# schematic.net
KiCad netlist of a schematic drawn in EasyEDA
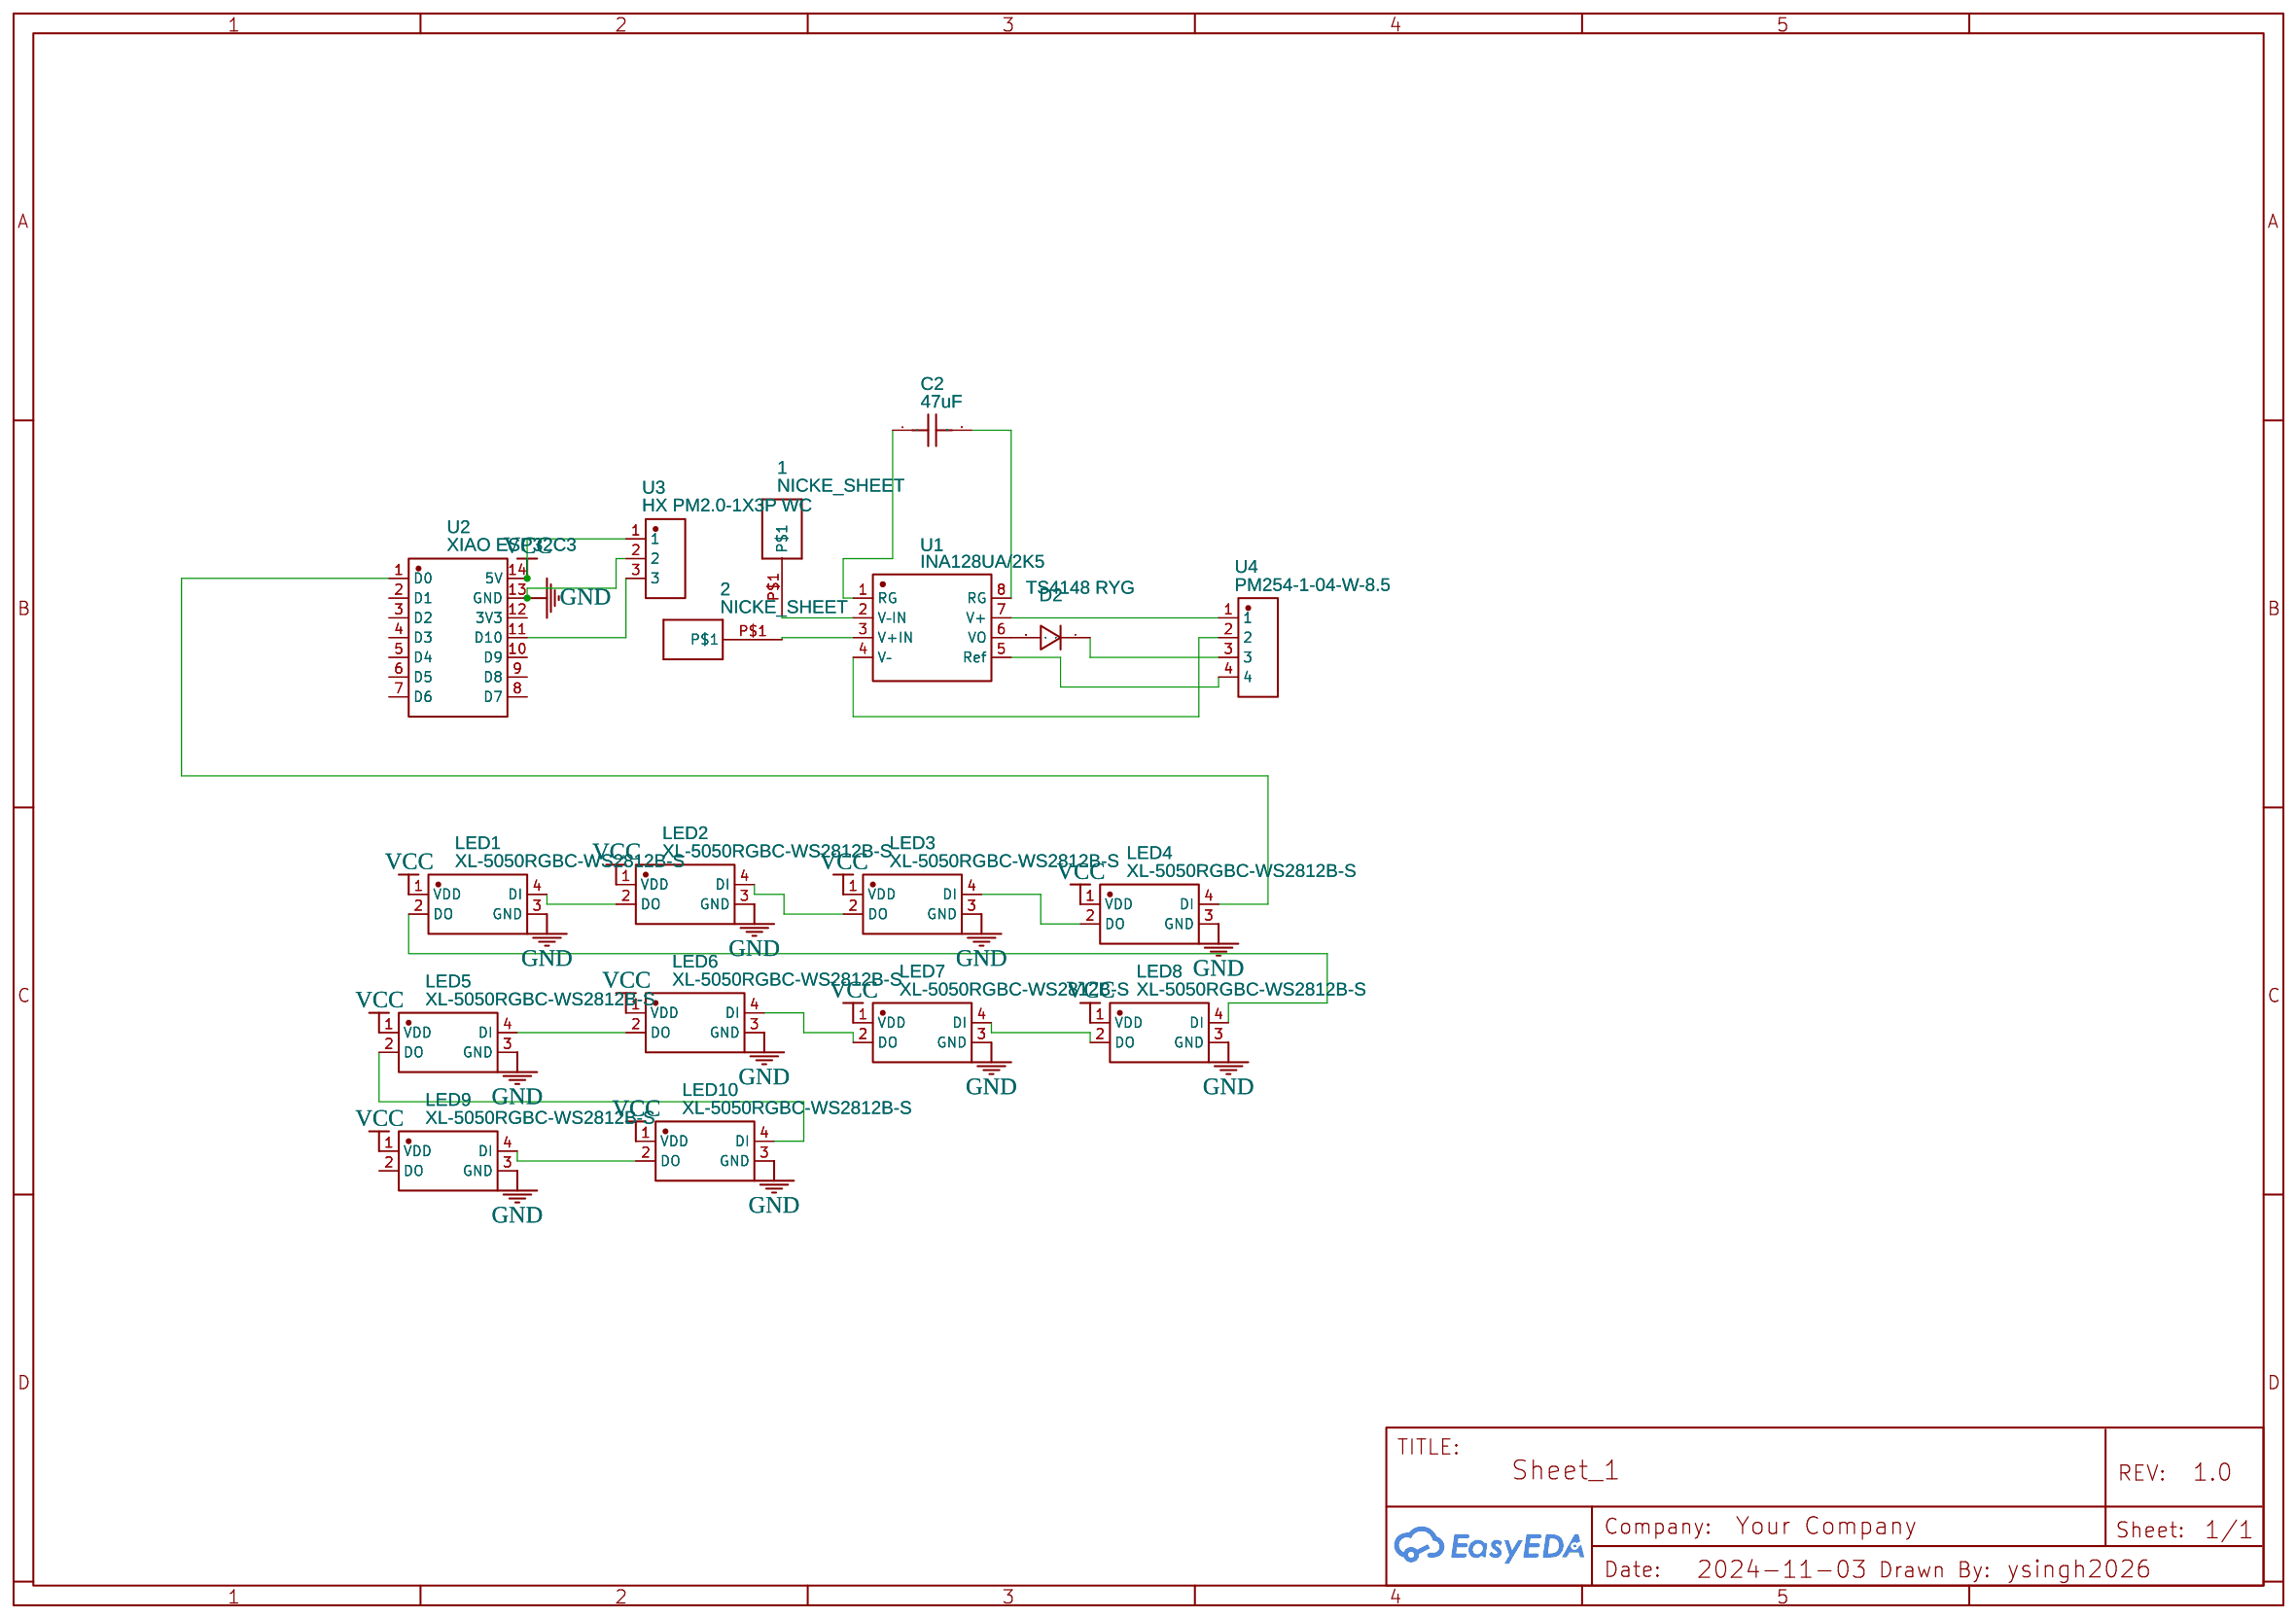
[diagram p0: schematic sheet]

(export (version "E")
  (design (tool "Eeschema 10.0.6"))
  (components
    (comp (ref "1") (value "NICKE_SHEET") (libsource (lib "") (part "NICKE_SHEET")))
    (comp (ref "2") (value "NICKE_SHEET") (libsource (lib "") (part "NICKE_SHEET_1")))
    (comp (ref "C2")
      (value "47uF")
      (fields
        (field (name "Manufacturer Part") "CS3225X7R476K100NRL")
        (field (name "Manufacturer") "SAMWHA(三和)")
      )
      (libsource (lib "") (part "CS3225X7R476K100NRL"))
    )
    (comp (ref "D2")
      (value "TS4148 RYG")
      (fields (field (name "Manufacturer") "Taiwan Semiconductor(台湾半导体)"))
      (libsource (lib "") (part "TS4148 RYG"))
    )
    (comp (ref "LED1")
      (value "XL-5050RGBC-WS2812B-S")
      (fields (field (name "Manufacturer") "XINGLIGHT(成兴光)"))
      (libsource (lib "") (part "XL-5050RGBC-WS2812B-S"))
    )
    (comp (ref "LED2")
      (value "XL-5050RGBC-WS2812B-S")
      (fields (field (name "Manufacturer") "XINGLIGHT(成兴光)"))
      (libsource (lib "") (part "XL-5050RGBC-WS2812B-S"))
    )
    (comp (ref "LED3")
      (value "XL-5050RGBC-WS2812B-S")
      (fields (field (name "Manufacturer") "XINGLIGHT(成兴光)"))
      (libsource (lib "") (part "XL-5050RGBC-WS2812B-S"))
    )
    (comp (ref "LED4")
      (value "XL-5050RGBC-WS2812B-S")
      (fields (field (name "Manufacturer") "XINGLIGHT(成兴光)"))
      (libsource (lib "") (part "XL-5050RGBC-WS2812B-S"))
    )
    (comp (ref "LED5")
      (value "XL-5050RGBC-WS2812B-S")
      (fields (field (name "Manufacturer") "XINGLIGHT(成兴光)"))
      (libsource (lib "") (part "XL-5050RGBC-WS2812B-S"))
    )
    (comp (ref "LED6")
      (value "XL-5050RGBC-WS2812B-S")
      (fields (field (name "Manufacturer") "XINGLIGHT(成兴光)"))
      (libsource (lib "") (part "XL-5050RGBC-WS2812B-S"))
    )
    (comp (ref "LED7")
      (value "XL-5050RGBC-WS2812B-S")
      (fields (field (name "Manufacturer") "XINGLIGHT(成兴光)"))
      (libsource (lib "") (part "XL-5050RGBC-WS2812B-S"))
    )
    (comp (ref "LED8")
      (value "XL-5050RGBC-WS2812B-S")
      (fields (field (name "Manufacturer") "XINGLIGHT(成兴光)"))
      (libsource (lib "") (part "XL-5050RGBC-WS2812B-S"))
    )
    (comp (ref "LED9")
      (value "XL-5050RGBC-WS2812B-S")
      (fields (field (name "Manufacturer") "XINGLIGHT(成兴光)"))
      (libsource (lib "") (part "XL-5050RGBC-WS2812B-S"))
    )
    (comp (ref "LED10")
      (value "XL-5050RGBC-WS2812B-S")
      (fields (field (name "Manufacturer") "XINGLIGHT(成兴光)"))
      (libsource (lib "") (part "XL-5050RGBC-WS2812B-S"))
    )
    (comp (ref "U1")
      (value "INA128UA/2K5")
      (fields (field (name "Manufacturer") "TI(德州仪器)"))
      (libsource (lib "") (part "INA128UA/2K5"))
    )
    (comp (ref "U2") (value "XIAO ESP32C3") (libsource (lib "") (part "XIAO ESP32C3")))
    (comp (ref "U3")
      (value "HX PM2.0-1X3P WC")
      (fields
        (field (name "Manufacturer Part") "HX PM2.0-1x3P WC")
        (field (name "Manufacturer") "hanxia(韩下)")
      )
      (libsource (lib "") (part "HX PM2.0-1X3P WC"))
    )
    (comp (ref "U4")
      (value "PM254-1-04-W-8.5")
      (fields (field (name "Manufacturer") "HCTL(华灿天禄)"))
      (libsource (lib "") (part "PM254-1-04-W-8.5"))
    )
  )
  (nets
    (net (code "1") (name "GND") (class "Default")
      (node (ref "LED1") (pin "3") (pinfunction "GND_3") (pintype "unspecified"))
      (node (ref "LED10") (pin "3") (pinfunction "GND_3") (pintype "unspecified"))
      (node (ref "LED2") (pin "3") (pinfunction "GND_3") (pintype "unspecified"))
      (node (ref "LED3") (pin "3") (pinfunction "GND_3") (pintype "unspecified"))
      (node (ref "LED4") (pin "3") (pinfunction "GND_3") (pintype "unspecified"))
      (node (ref "LED5") (pin "3") (pinfunction "GND_3") (pintype "unspecified"))
      (node (ref "LED6") (pin "3") (pinfunction "GND_3") (pintype "unspecified"))
      (node (ref "LED7") (pin "3") (pinfunction "GND_3") (pintype "unspecified"))
      (node (ref "LED8") (pin "3") (pinfunction "GND_3") (pintype "unspecified"))
      (node (ref "LED9") (pin "3") (pinfunction "GND_3") (pintype "unspecified"))
      (node (ref "U2") (pin "13") (pinfunction "GND_13") (pintype "unspecified"))
      (node (ref "U3") (pin "2") (pinfunction "2_2") (pintype "unspecified"))
    )
    (net (code "2") (name "Net-(C2-Pad1)") (class "Default")
      (node (ref "C2") (pin "1") (pinfunction "1_1") (pintype "unspecified"))
      (node (ref "U1") (pin "1") (pinfunction "RG_1") (pintype "unspecified"))
    )
    (net (code "3") (name "Net-(C2-Pad2)") (class "Default")
      (node (ref "C2") (pin "2") (pinfunction "2_2") (pintype "unspecified"))
      (node (ref "U1") (pin "8") (pinfunction "RG_8") (pintype "unspecified"))
    )
    (net (code "4") (name "Net-(D2-Pad1)") (class "Default")
      (node (ref "D2") (pin "1") (pinfunction "1_1") (pintype "unspecified"))
      (node (ref "U4") (pin "3") (pinfunction "3_3") (pintype "unspecified"))
    )
    (net (code "5") (name "Net-(LED1-DI)") (class "Default")
      (node (ref "LED1") (pin "4") (pinfunction "DI_4") (pintype "unspecified"))
      (node (ref "LED2") (pin "2") (pinfunction "DO_2") (pintype "unspecified"))
    )
    (net (code "6") (name "Net-(LED1-DO)") (class "Default")
      (node (ref "LED1") (pin "2") (pinfunction "DO_2") (pintype "unspecified"))
      (node (ref "LED8") (pin "4") (pinfunction "DI_4") (pintype "unspecified"))
    )
    (net (code "7") (name "Net-(LED2-DI)") (class "Default")
      (node (ref "LED2") (pin "4") (pinfunction "DI_4") (pintype "unspecified"))
      (node (ref "LED3") (pin "2") (pinfunction "DO_2") (pintype "unspecified"))
    )
    (net (code "8") (name "Net-(LED3-DI)") (class "Default")
      (node (ref "LED3") (pin "4") (pinfunction "DI_4") (pintype "unspecified"))
      (node (ref "LED4") (pin "2") (pinfunction "DO_2") (pintype "unspecified"))
    )
    (net (code "9") (name "Net-(LED4-DI)") (class "Default")
      (node (ref "LED4") (pin "4") (pinfunction "DI_4") (pintype "unspecified"))
      (node (ref "U2") (pin "1") (pinfunction "D0_1") (pintype "unspecified"))
    )
    (net (code "10") (name "Net-(LED5-DI)") (class "Default")
      (node (ref "LED5") (pin "4") (pinfunction "DI_4") (pintype "unspecified"))
      (node (ref "LED6") (pin "2") (pinfunction "DO_2") (pintype "unspecified"))
    )
    (net (code "11") (name "Net-(LED6-DI)") (class "Default")
      (node (ref "LED6") (pin "4") (pinfunction "DI_4") (pintype "unspecified"))
      (node (ref "LED7") (pin "2") (pinfunction "DO_2") (pintype "unspecified"))
    )
    (net (code "12") (name "Net-(LED7-DI)") (class "Default")
      (node (ref "LED7") (pin "4") (pinfunction "DI_4") (pintype "unspecified"))
      (node (ref "LED8") (pin "2") (pinfunction "DO_2") (pintype "unspecified"))
    )
    (net (code "13") (name "Net-(LED10-DI)") (class "Default")
      (node (ref "LED10") (pin "4") (pinfunction "DI_4") (pintype "unspecified"))
      (node (ref "LED5") (pin "2") (pinfunction "DO_2") (pintype "unspecified"))
    )
    (net (code "14") (name "Net-(LED10-DO)") (class "Default")
      (node (ref "LED10") (pin "2") (pinfunction "DO_2") (pintype "unspecified"))
      (node (ref "LED9") (pin "4") (pinfunction "DI_4") (pintype "unspecified"))
    )
    (net (code "15") (name "Net-(U1-Ref)") (class "Default")
      (node (ref "U1") (pin "5") (pinfunction "Ref_5") (pintype "unspecified"))
      (node (ref "U4") (pin "4") (pinfunction "4_4") (pintype "unspecified"))
    )
    (net (code "16") (name "Net-(U1-V+)") (class "Default")
      (node (ref "U1") (pin "7") (pinfunction "V+_7") (pintype "unspecified"))
      (node (ref "U4") (pin "1") (pinfunction "1_1") (pintype "unspecified"))
    )
    (net (code "17") (name "Net-(U1-V+IN)") (class "Default")
      (node (ref "2") (pin "P$1") (pinfunction "P$1_P$1") (pintype "bidirectional"))
      (node (ref "U1") (pin "3") (pinfunction "V+IN_3") (pintype "unspecified"))
    )
    (net (code "18") (name "Net-(U1-VO)") (class "Default")
      (node (ref "D2") (pin "2") (pinfunction "2_2") (pintype "unspecified"))
      (node (ref "U1") (pin "6") (pinfunction "VO_6") (pintype "unspecified"))
    )
    (net (code "19") (name "Net-(U1-V–)") (class "Default")
      (node (ref "U1") (pin "4") (pinfunction "V–_4") (pintype "unspecified"))
      (node (ref "U4") (pin "2") (pinfunction "2_2") (pintype "unspecified"))
    )
    (net (code "20") (name "Net-(U1-V–IN)") (class "Default")
      (node (ref "1") (pin "P$1") (pinfunction "P$1_P$1") (pintype "bidirectional"))
      (node (ref "U1") (pin "2") (pinfunction "V–IN_2") (pintype "unspecified"))
    )
    (net (code "21") (name "Net-(U2-D10)") (class "Default")
      (node (ref "U2") (pin "11") (pinfunction "D10_11") (pintype "unspecified"))
      (node (ref "U3") (pin "3") (pinfunction "3_3") (pintype "unspecified"))
    )
    (net (code "22") (name "VCC") (class "Default")
      (node (ref "LED1") (pin "1") (pinfunction "VDD_1") (pintype "unspecified"))
      (node (ref "LED10") (pin "1") (pinfunction "VDD_1") (pintype "unspecified"))
      (node (ref "LED2") (pin "1") (pinfunction "VDD_1") (pintype "unspecified"))
      (node (ref "LED3") (pin "1") (pinfunction "VDD_1") (pintype "unspecified"))
      (node (ref "LED4") (pin "1") (pinfunction "VDD_1") (pintype "unspecified"))
      (node (ref "LED5") (pin "1") (pinfunction "VDD_1") (pintype "unspecified"))
      (node (ref "LED6") (pin "1") (pinfunction "VDD_1") (pintype "unspecified"))
      (node (ref "LED7") (pin "1") (pinfunction "VDD_1") (pintype "unspecified"))
      (node (ref "LED8") (pin "1") (pinfunction "VDD_1") (pintype "unspecified"))
      (node (ref "LED9") (pin "1") (pinfunction "VDD_1") (pintype "unspecified"))
      (node (ref "U2") (pin "14") (pinfunction "5V_14") (pintype "unspecified"))
      (node (ref "U3") (pin "1") (pinfunction "1_1") (pintype "unspecified"))
    )
    (net (code "23") (name "unconnected-(LED9-DO-Pad2)") (class "Default")
      (node (ref "LED9") (pin "2") (pinfunction "DO_2") (pintype "unspecified"))
    )
    (net (code "24") (name "unconnected-(U2-3V3-Pad12)") (class "Default")
      (node (ref "U2") (pin "12") (pinfunction "3V3_12") (pintype "unspecified"))
    )
    (net (code "25") (name "unconnected-(U2-D1-Pad2)") (class "Default")
      (node (ref "U2") (pin "2") (pinfunction "D1_2") (pintype "unspecified"))
    )
    (net (code "26") (name "unconnected-(U2-D2-Pad3)") (class "Default")
      (node (ref "U2") (pin "3") (pinfunction "D2_3") (pintype "unspecified"))
    )
    (net (code "27") (name "unconnected-(U2-D3-Pad4)") (class "Default")
      (node (ref "U2") (pin "4") (pinfunction "D3_4") (pintype "unspecified"))
    )
    (net (code "28") (name "unconnected-(U2-D4-Pad5)") (class "Default")
      (node (ref "U2") (pin "5") (pinfunction "D4_5") (pintype "unspecified"))
    )
    (net (code "29") (name "unconnected-(U2-D5-Pad6)") (class "Default")
      (node (ref "U2") (pin "6") (pinfunction "D5_6") (pintype "unspecified"))
    )
    (net (code "30") (name "unconnected-(U2-D6-Pad7)") (class "Default")
      (node (ref "U2") (pin "7") (pinfunction "D6_7") (pintype "unspecified"))
    )
    (net (code "31") (name "unconnected-(U2-D7-Pad8)") (class "Default")
      (node (ref "U2") (pin "8") (pinfunction "D7_8") (pintype "unspecified"))
    )
    (net (code "32") (name "unconnected-(U2-D8-Pad9)") (class "Default")
      (node (ref "U2") (pin "9") (pinfunction "D8_9") (pintype "unspecified"))
    )
    (net (code "33") (name "unconnected-(U2-D9-Pad10)") (class "Default")
      (node (ref "U2") (pin "10") (pinfunction "D9_10") (pintype "unspecified"))
    )
  )
)
